# Attenuation.net
KiCad netlist of a schematic drawn in EAGLE
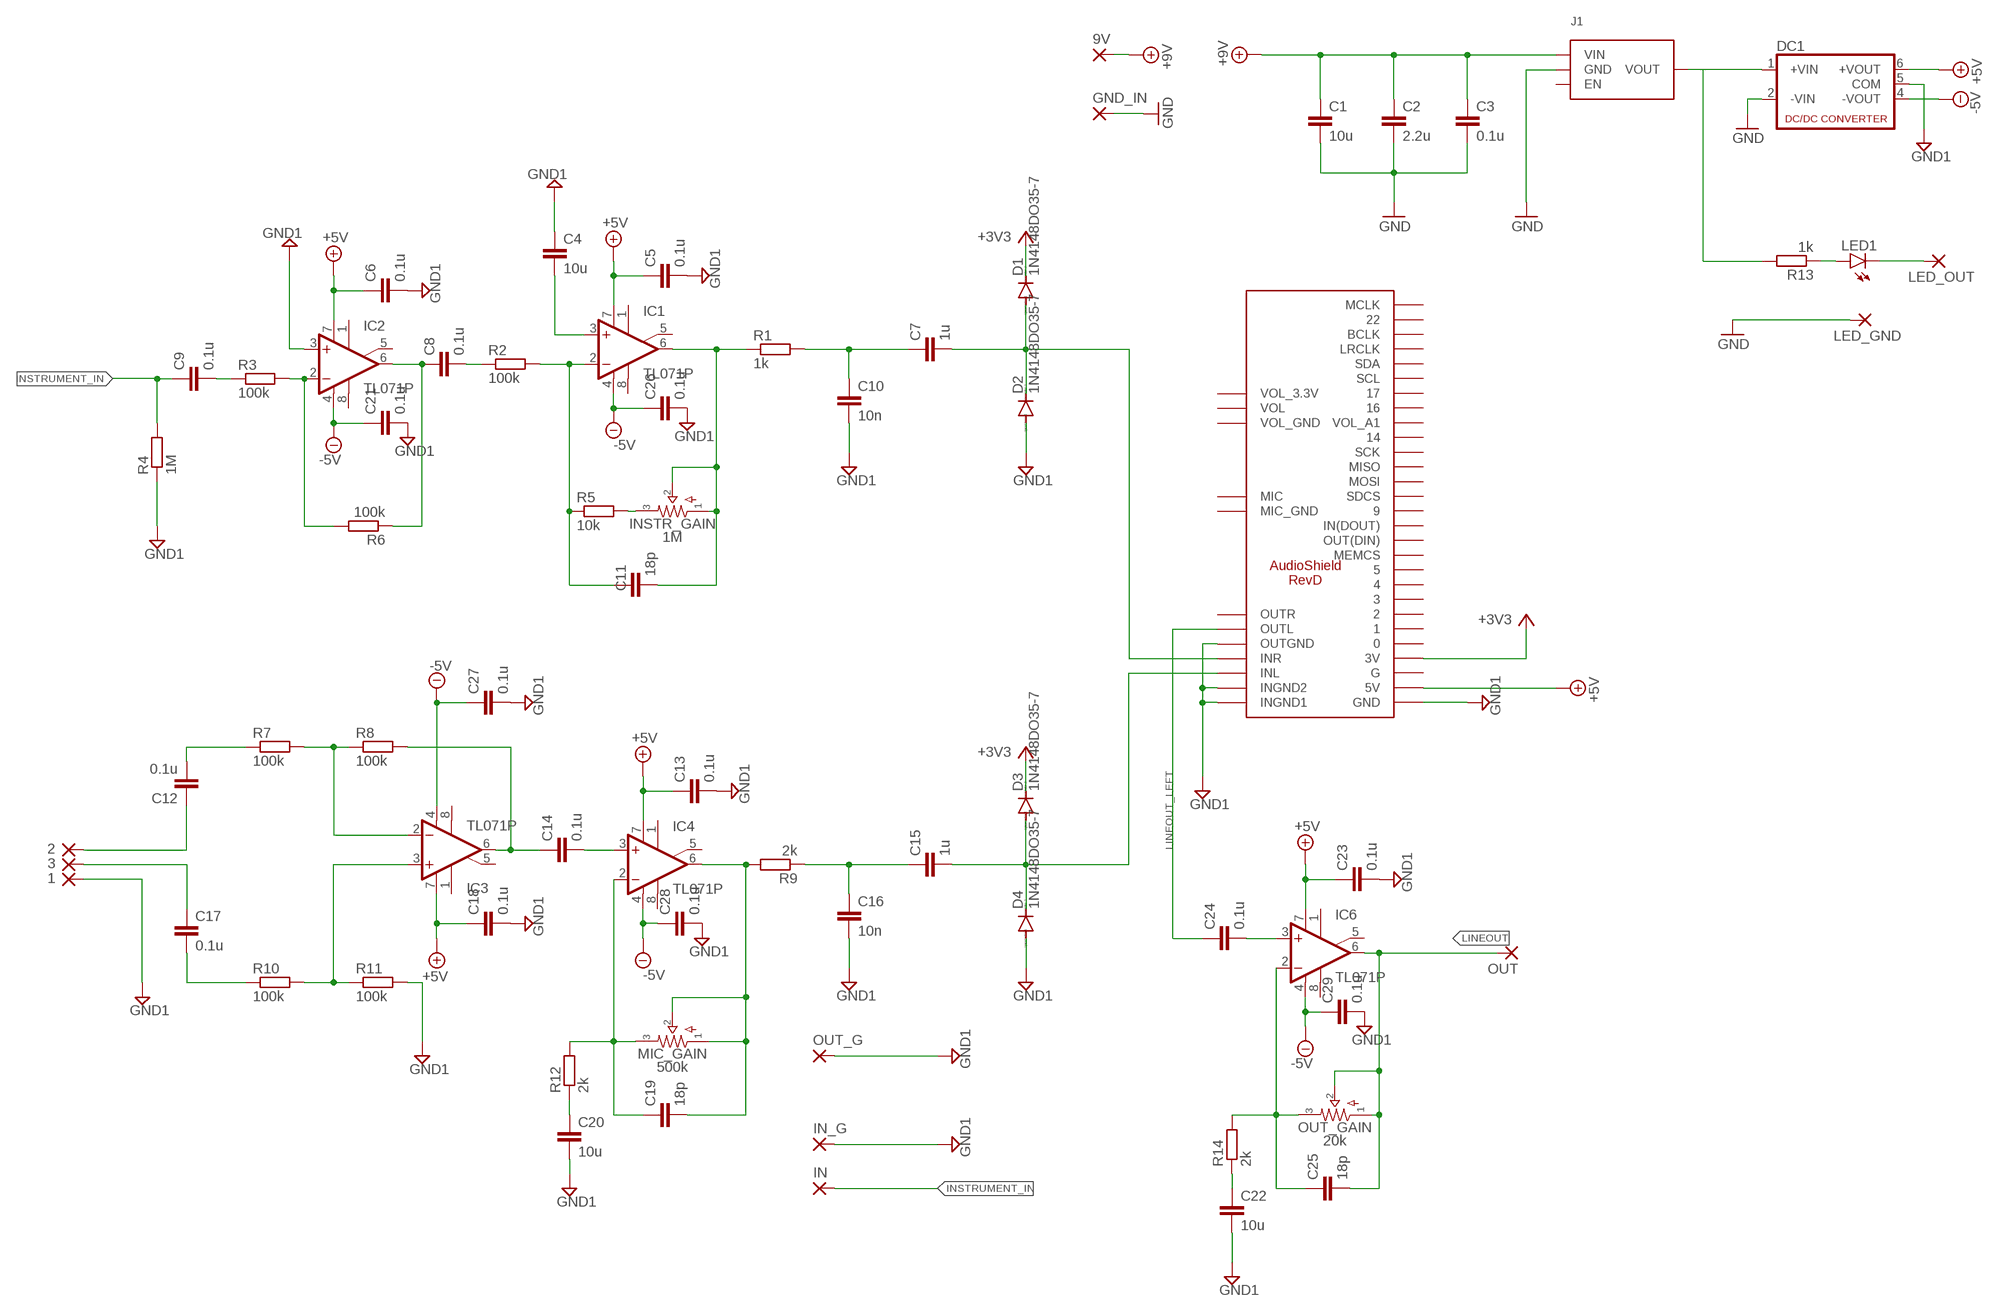
[diagram p0: schematic, sheet 1]

(export (version "E")
  (design (tool "Eeschema 10.0.6"))
  (components
    (comp (ref "1")
      (value "1,6/0,8")
      (footprint "eagle-import:1,6_0,8")
      (libsource (lib "eagle-import") (part "1,6/0,8"))
    )
    (comp (ref "2")
      (value "1,6/0,8")
      (footprint "eagle-import:1,6_0,8")
      (libsource (lib "eagle-import") (part "1,6/0,8"))
    )
    (comp (ref "3")
      (value "1,6/0,8")
      (footprint "eagle-import:1,6_0,8")
      (libsource (lib "eagle-import") (part "1,6/0,8"))
    )
    (comp (ref "9V")
      (value "1,6/0,8")
      (footprint "eagle-import:1,6_0,8")
      (libsource (lib "eagle-import") (part "1,6/0,8"))
    )
    (comp (ref "C1")
      (value "10u")
      (footprint "eagle-import:C5B2.5")
      (libsource (lib "eagle-import") (part "C5/2.5"))
    )
    (comp (ref "C2")
      (value "2.2u")
      (footprint "eagle-import:C5B2.5")
      (libsource (lib "eagle-import") (part "C5/2.5"))
    )
    (comp (ref "C3")
      (value "0.1u")
      (footprint "eagle-import:C0805")
      (libsource (lib "eagle-import") (part "C-EUC0805"))
    )
    (comp (ref "C4")
      (value "10u")
      (footprint "eagle-import:C5B2.5")
      (libsource (lib "eagle-import") (part "C5/2.5"))
    )
    (comp (ref "C5")
      (value "0.1u")
      (footprint "eagle-import:C0805")
      (libsource (lib "eagle-import") (part "C-EUC0805"))
    )
    (comp (ref "C6")
      (value "0.1u")
      (footprint "eagle-import:C0805")
      (libsource (lib "eagle-import") (part "C-EUC0805"))
    )
    (comp (ref "C7")
      (value "1u")
      (footprint "eagle-import:C0805")
      (libsource (lib "eagle-import") (part "C-EUC0805"))
    )
    (comp (ref "C8")
      (value "0.1u")
      (footprint "eagle-import:C0805")
      (libsource (lib "eagle-import") (part "C-EUC0805"))
    )
    (comp (ref "C9")
      (value "0.1u")
      (footprint "eagle-import:C0805")
      (libsource (lib "eagle-import") (part "C-EUC0805"))
    )
    (comp (ref "C10")
      (value "10n")
      (footprint "eagle-import:C0805")
      (libsource (lib "eagle-import") (part "C-EUC0805"))
    )
    (comp (ref "C11")
      (value "18p")
      (footprint "eagle-import:C0805")
      (libsource (lib "eagle-import") (part "C-EUC0805"))
    )
    (comp (ref "C12")
      (value "0.1u")
      (footprint "eagle-import:C0805")
      (libsource (lib "eagle-import") (part "C-EUC0805"))
    )
    (comp (ref "C13")
      (value "0.1u")
      (footprint "eagle-import:C0805")
      (libsource (lib "eagle-import") (part "C-EUC0805"))
    )
    (comp (ref "C14")
      (value "0.1u")
      (footprint "eagle-import:C0805")
      (libsource (lib "eagle-import") (part "C-EUC0805"))
    )
    (comp (ref "C15")
      (value "1u")
      (footprint "eagle-import:C0805")
      (libsource (lib "eagle-import") (part "C-EUC0805"))
    )
    (comp (ref "C16")
      (value "10n")
      (footprint "eagle-import:C0805")
      (libsource (lib "eagle-import") (part "C-EUC0805"))
    )
    (comp (ref "C17")
      (value "0.1u")
      (footprint "eagle-import:C0805")
      (libsource (lib "eagle-import") (part "C-EUC0805"))
    )
    (comp (ref "C18")
      (value "0.1u")
      (footprint "eagle-import:C0805")
      (libsource (lib "eagle-import") (part "C-EUC0805"))
    )
    (comp (ref "C19")
      (value "18p")
      (footprint "eagle-import:C0805")
      (libsource (lib "eagle-import") (part "C-EUC0805"))
    )
    (comp (ref "C20")
      (value "10u")
      (footprint "eagle-import:C5B2.5")
      (libsource (lib "eagle-import") (part "C5/2.5"))
    )
    (comp (ref "C21")
      (value "0.1u")
      (footprint "eagle-import:C0805")
      (libsource (lib "eagle-import") (part "C-EUC0805"))
    )
    (comp (ref "C22")
      (value "10u")
      (footprint "eagle-import:C5B2.5")
      (libsource (lib "eagle-import") (part "C5/2.5"))
    )
    (comp (ref "C23")
      (value "0.1u")
      (footprint "eagle-import:C0805")
      (libsource (lib "eagle-import") (part "C-EUC0805"))
    )
    (comp (ref "C24")
      (value "0.1u")
      (footprint "eagle-import:C0805")
      (libsource (lib "eagle-import") (part "C-EUC0805"))
    )
    (comp (ref "C25")
      (value "18p")
      (footprint "eagle-import:C0805")
      (libsource (lib "eagle-import") (part "C-EUC0805"))
    )
    (comp (ref "C26")
      (value "0.1u")
      (footprint "eagle-import:C0805")
      (libsource (lib "eagle-import") (part "C-EUC0805"))
    )
    (comp (ref "C27")
      (value "0.1u")
      (footprint "eagle-import:C0805")
      (libsource (lib "eagle-import") (part "C-EUC0805"))
    )
    (comp (ref "C28")
      (value "0.1u")
      (footprint "eagle-import:C0805")
      (libsource (lib "eagle-import") (part "C-EUC0805"))
    )
    (comp (ref "C29")
      (value "0.1u")
      (footprint "eagle-import:C0805")
      (libsource (lib "eagle-import") (part "C-EUC0805"))
    )
    (comp (ref "D1")
      (value "1N4148DO35-7")
      (footprint "eagle-import:DO35-7")
      (libsource (lib "eagle-import") (part "1N4148DO35-7"))
    )
    (comp (ref "D2")
      (value "1N4148DO35-7")
      (footprint "eagle-import:DO35-7")
      (libsource (lib "eagle-import") (part "1N4148DO35-7"))
    )
    (comp (ref "D3")
      (value "1N4148DO35-7")
      (footprint "eagle-import:DO35-7")
      (libsource (lib "eagle-import") (part "1N4148DO35-7"))
    )
    (comp (ref "D4")
      (value "1N4148DO35-7")
      (footprint "eagle-import:DO35-7")
      (libsource (lib "eagle-import") (part "1N4148DO35-7"))
    )
    (comp (ref "DC1")
      (value "NMA")
      (footprint "eagle-import:NMA")
      (fields (field (name "MF") "C & D TECHNOLOGIES, INC") (field (name "MPN") "NMA0515SC"))
      (libsource (lib "eagle-import") (part "NMA"))
    )
    (comp (ref "GND_IN")
      (value "1,6/0,8")
      (footprint "eagle-import:1,6_0,8")
      (libsource (lib "eagle-import") (part "1,6/0,8"))
    )
    (comp (ref "IC1")
      (value "TL071P")
      (footprint "eagle-import:DIL08")
      (libsource (lib "eagle-import") (part "TL071P"))
    )
    (comp (ref "IC2")
      (value "TL071P")
      (footprint "eagle-import:DIL08")
      (libsource (lib "eagle-import") (part "TL071P"))
    )
    (comp (ref "IC3")
      (value "TL071P")
      (footprint "eagle-import:DIL08")
      (libsource (lib "eagle-import") (part "TL071P"))
    )
    (comp (ref "IC4")
      (value "TL071P")
      (footprint "eagle-import:DIL08")
      (libsource (lib "eagle-import") (part "TL071P"))
    )
    (comp (ref "IC6")
      (value "TL071P")
      (footprint "eagle-import:DIL08")
      (libsource (lib "eagle-import") (part "TL071P"))
    )
    (comp (ref "IN")
      (value "1,6/0,8")
      (footprint "eagle-import:1,6_0,8")
      (libsource (lib "eagle-import") (part "1,6/0,8"))
    )
    (comp (ref "INSTR_GAIN")
      (value "1M")
      (footprint "eagle-import:16MM_PADS.1")
      (libsource (lib "eagle-import") (part "16MM.4"))
    )
    (comp (ref "IN_G")
      (value "1,6/0,8")
      (footprint "eagle-import:1,6_0,8")
      (libsource (lib "eagle-import") (part "1,6/0,8"))
    )
    (comp (ref "J1")
      (value "DCDC_MINI_CONVERTER")
      (footprint "eagle-import:DCDC_MINI_CONVERTER")
      (libsource (lib "eagle-import") (part "DCDC_MINI_CONVERTER"))
    )
    (comp (ref "LED1")
      (value "LED5MM")
      (footprint "eagle-import:LED5MM")
      (libsource (lib "eagle-import") (part "LED5MM"))
    )
    (comp (ref "LED_GND")
      (value "1,6/0,8")
      (footprint "eagle-import:1,6_0,8")
      (libsource (lib "eagle-import") (part "1,6/0,8"))
    )
    (comp (ref "LED_OUT")
      (value "1,6/0,8")
      (footprint "eagle-import:1,6_0,8")
      (libsource (lib "eagle-import") (part "1,6/0,8"))
    )
    (comp (ref "MIC_GAIN")
      (value "500k")
      (footprint "eagle-import:16MM_PADS.1")
      (libsource (lib "eagle-import") (part "16MM.4"))
    )
    (comp (ref "MOD1")
      (value "AUDIOSHIELD-REVD")
      (footprint "eagle-import:AUDIOSHIELD-REVD")
      (libsource (lib "eagle-import") (part "AUDIOSHIELD-REVD"))
    )
    (comp (ref "OUT")
      (value "1,6/0,8")
      (footprint "eagle-import:1,6_0,8")
      (libsource (lib "eagle-import") (part "1,6/0,8"))
    )
    (comp (ref "OUT_G")
      (value "1,6/0,8")
      (footprint "eagle-import:1,6_0,8")
      (libsource (lib "eagle-import") (part "1,6/0,8"))
    )
    (comp (ref "OUT_GAIN")
      (value "20k")
      (footprint "eagle-import:16MM_PADS.1")
      (libsource (lib "eagle-import") (part "16MM.4"))
    )
    (comp (ref "R1")
      (value "1k")
      (footprint "eagle-import:R0805")
      (libsource (lib "eagle-import") (part "R-EU_R0805"))
    )
    (comp (ref "R2")
      (value "100k")
      (footprint "eagle-import:R0805")
      (libsource (lib "eagle-import") (part "R-EU_R0805"))
    )
    (comp (ref "R3")
      (value "100k")
      (footprint "eagle-import:R0805")
      (libsource (lib "eagle-import") (part "R-EU_R0805"))
    )
    (comp (ref "R4")
      (value "1M")
      (footprint "eagle-import:R0805")
      (libsource (lib "eagle-import") (part "R-EU_R0805"))
    )
    (comp (ref "R5")
      (value "10k")
      (footprint "eagle-import:R0805")
      (libsource (lib "eagle-import") (part "R-EU_R0805"))
    )
    (comp (ref "R6")
      (value "100k")
      (footprint "eagle-import:R0805")
      (libsource (lib "eagle-import") (part "R-EU_R0805"))
    )
    (comp (ref "R7")
      (value "100k")
      (footprint "eagle-import:R0805")
      (libsource (lib "eagle-import") (part "R-EU_R0805"))
    )
    (comp (ref "R8")
      (value "100k")
      (footprint "eagle-import:R0805")
      (libsource (lib "eagle-import") (part "R-EU_R0805"))
    )
    (comp (ref "R9")
      (value "2k")
      (footprint "eagle-import:R0805")
      (libsource (lib "eagle-import") (part "R-EU_R0805"))
    )
    (comp (ref "R10")
      (value "100k")
      (footprint "eagle-import:R0805")
      (libsource (lib "eagle-import") (part "R-EU_R0805"))
    )
    (comp (ref "R11")
      (value "100k")
      (footprint "eagle-import:R0805")
      (libsource (lib "eagle-import") (part "R-EU_R0805"))
    )
    (comp (ref "R12")
      (value "2k")
      (footprint "eagle-import:R0805")
      (libsource (lib "eagle-import") (part "R-EU_R0805"))
    )
    (comp (ref "R13")
      (value "1k")
      (footprint "eagle-import:R0805")
      (libsource (lib "eagle-import") (part "R-EU_R0805"))
    )
    (comp (ref "R14")
      (value "2k")
      (footprint "eagle-import:R0805")
      (libsource (lib "eagle-import") (part "R-EU_R0805"))
    )
  )
  (nets
    (net (code "1") (name "+3V3") (class "Default")
      (node (ref "D1") (pin "C") (pinfunction "C_C") (pintype "passive"))
      (node (ref "D3") (pin "C") (pinfunction "C_C") (pintype "passive"))
      (node (ref "MOD1") (pin "3V") (pinfunction "3V_3V") (pintype "bidirectional"))
    )
    (net (code "2") (name "+5V") (class "Default")
      (node (ref "C13") (pin "1") (pinfunction "1_1") (pintype "passive"))
      (node (ref "C18") (pin "1") (pinfunction "1_1") (pintype "passive"))
      (node (ref "C23") (pin "1") (pinfunction "1_1") (pintype "passive"))
      (node (ref "C5") (pin "1") (pinfunction "1_1") (pintype "passive"))
      (node (ref "C6") (pin "1") (pinfunction "1_1") (pintype "passive"))
      (node (ref "DC1") (pin "6") (pinfunction "+VOUT_6") (pintype "passive"))
      (node (ref "IC1") (pin "7") (pinfunction "V+_7") (pintype "power_in"))
      (node (ref "IC2") (pin "7") (pinfunction "V+_7") (pintype "power_in"))
      (node (ref "IC3") (pin "7") (pinfunction "V+_7") (pintype "power_in"))
      (node (ref "IC4") (pin "7") (pinfunction "V+_7") (pintype "power_in"))
      (node (ref "IC6") (pin "7") (pinfunction "V+_7") (pintype "power_in"))
      (node (ref "MOD1") (pin "5V") (pinfunction "5V_5V") (pintype "bidirectional"))
    )
    (net (code "3") (name "+9V") (class "Default")
      (node (ref "9V") (pin "1") (pinfunction "P_1") (pintype "passive"))
      (node (ref "C1") (pin "1") (pinfunction "1_1") (pintype "passive"))
      (node (ref "C2") (pin "1") (pinfunction "1_1") (pintype "passive"))
      (node (ref "C3") (pin "1") (pinfunction "1_1") (pintype "passive"))
      (node (ref "J1") (pin "VIN") (pinfunction "VIN_VIN") (pintype "bidirectional"))
    )
    (net (code "4") (name "-5V") (class "Default")
      (node (ref "C21") (pin "1") (pinfunction "1_1") (pintype "passive"))
      (node (ref "C26") (pin "1") (pinfunction "1_1") (pintype "passive"))
      (node (ref "C27") (pin "1") (pinfunction "1_1") (pintype "passive"))
      (node (ref "C28") (pin "1") (pinfunction "1_1") (pintype "passive"))
      (node (ref "C29") (pin "1") (pinfunction "1_1") (pintype "passive"))
      (node (ref "DC1") (pin "4") (pinfunction "-VOUT_4") (pintype "passive"))
      (node (ref "IC1") (pin "4") (pinfunction "V-_4") (pintype "power_in"))
      (node (ref "IC2") (pin "4") (pinfunction "V-_4") (pintype "power_in"))
      (node (ref "IC3") (pin "4") (pinfunction "V-_4") (pintype "power_in"))
      (node (ref "IC4") (pin "4") (pinfunction "V-_4") (pintype "power_in"))
      (node (ref "IC6") (pin "4") (pinfunction "V-_4") (pintype "power_in"))
    )
    (net (code "5") (name "/LINEOUT_LEFT") (class "Default")
      (node (ref "C24") (pin "1") (pinfunction "1_1") (pintype "passive"))
      (node (ref "MOD1") (pin "OUTL") (pinfunction "OUTL_OUTL") (pintype "output"))
    )
    (net (code "6") (name "GND") (class "Default")
      (node (ref "C1") (pin "2") (pinfunction "2_2") (pintype "passive"))
      (node (ref "C2") (pin "2") (pinfunction "2_2") (pintype "passive"))
      (node (ref "C3") (pin "2") (pinfunction "2_2") (pintype "passive"))
      (node (ref "DC1") (pin "2") (pinfunction "-VIN_2") (pintype "passive"))
      (node (ref "GND_IN") (pin "1") (pinfunction "P_1") (pintype "passive"))
      (node (ref "J1") (pin "GND") (pinfunction "GND_GND") (pintype "bidirectional"))
      (node (ref "LED_GND") (pin "1") (pinfunction "P_1") (pintype "passive"))
    )
    (net (code "7") (name "GND1") (class "Default")
      (node (ref "1") (pin "1") (pinfunction "P_1") (pintype "passive"))
      (node (ref "C10") (pin "2") (pinfunction "2_2") (pintype "passive"))
      (node (ref "C13") (pin "2") (pinfunction "2_2") (pintype "passive"))
      (node (ref "C16") (pin "2") (pinfunction "2_2") (pintype "passive"))
      (node (ref "C18") (pin "2") (pinfunction "2_2") (pintype "passive"))
      (node (ref "C20") (pin "2") (pinfunction "2_2") (pintype "passive"))
      (node (ref "C21") (pin "2") (pinfunction "2_2") (pintype "passive"))
      (node (ref "C22") (pin "2") (pinfunction "2_2") (pintype "passive"))
      (node (ref "C23") (pin "2") (pinfunction "2_2") (pintype "passive"))
      (node (ref "C26") (pin "2") (pinfunction "2_2") (pintype "passive"))
      (node (ref "C27") (pin "2") (pinfunction "2_2") (pintype "passive"))
      (node (ref "C28") (pin "2") (pinfunction "2_2") (pintype "passive"))
      (node (ref "C29") (pin "2") (pinfunction "2_2") (pintype "passive"))
      (node (ref "C4") (pin "1") (pinfunction "1_1") (pintype "passive"))
      (node (ref "C5") (pin "2") (pinfunction "2_2") (pintype "passive"))
      (node (ref "C6") (pin "2") (pinfunction "2_2") (pintype "passive"))
      (node (ref "D2") (pin "A") (pinfunction "A_A") (pintype "passive"))
      (node (ref "D4") (pin "A") (pinfunction "A_A") (pintype "passive"))
      (node (ref "DC1") (pin "5") (pinfunction "COM_5") (pintype "passive"))
      (node (ref "IC2") (pin "3") (pinfunction "+IN_3") (pintype "input"))
      (node (ref "IN_G") (pin "1") (pinfunction "P_1") (pintype "passive"))
      (node (ref "MOD1") (pin "GND") (pinfunction "GND_GND") (pintype "bidirectional"))
      (node (ref "MOD1") (pin "INGND1") (pinfunction "INGND1_INGND1") (pintype "bidirectional"))
      (node (ref "MOD1") (pin "INGND2") (pinfunction "INGND2_INGND2") (pintype "bidirectional"))
      (node (ref "MOD1") (pin "OUTGND") (pinfunction "OUTGND_OUTGND") (pintype "bidirectional"))
      (node (ref "OUT_G") (pin "1") (pinfunction "P_1") (pintype "passive"))
      (node (ref "R11") (pin "2") (pinfunction "2_2") (pintype "passive"))
      (node (ref "R4") (pin "1") (pinfunction "1_1") (pintype "passive"))
    )
    (net (code "8") (name "INSTRUMENT_IN") (class "Default")
      (node (ref "C9") (pin "1") (pinfunction "1_1") (pintype "passive"))
      (node (ref "IN") (pin "1") (pinfunction "P_1") (pintype "passive"))
      (node (ref "R4") (pin "2") (pinfunction "2_2") (pintype "passive"))
    )
    (net (code "9") (name "LINEOUT") (class "Default")
      (node (ref "C25") (pin "2") (pinfunction "2_2") (pintype "passive"))
      (node (ref "IC6") (pin "6") (pinfunction "OUT_6") (pintype "output"))
      (node (ref "OUT") (pin "1") (pinfunction "P_1") (pintype "passive"))
      (node (ref "OUT_GAIN") (pin "1") (pinfunction "1_1") (pintype "passive"))
      (node (ref "OUT_GAIN") (pin "2") (pinfunction "2_2") (pintype "passive"))
    )
    (net (code "10") (name "Net-(2-P)") (class "Default")
      (node (ref "2") (pin "1") (pinfunction "P_1") (pintype "passive"))
      (node (ref "C12") (pin "1") (pinfunction "1_1") (pintype "passive"))
    )
    (net (code "11") (name "Net-(3-P)") (class "Default")
      (node (ref "3") (pin "1") (pinfunction "P_1") (pintype "passive"))
      (node (ref "C17") (pin "1") (pinfunction "1_1") (pintype "passive"))
    )
    (net (code "12") (name "Net-(C7-Pad2)") (class "Default")
      (node (ref "C7") (pin "2") (pinfunction "2_2") (pintype "passive"))
      (node (ref "D1") (pin "A") (pinfunction "A_A") (pintype "passive"))
      (node (ref "D2") (pin "C") (pinfunction "C_C") (pintype "passive"))
      (node (ref "MOD1") (pin "INR") (pinfunction "INR_INR") (pintype "input"))
    )
    (net (code "13") (name "Net-(C8-Pad2)") (class "Default")
      (node (ref "C8") (pin "2") (pinfunction "2_2") (pintype "passive"))
      (node (ref "R2") (pin "1") (pinfunction "1_1") (pintype "passive"))
    )
    (net (code "14") (name "Net-(C9-Pad2)") (class "Default")
      (node (ref "C9") (pin "2") (pinfunction "2_2") (pintype "passive"))
      (node (ref "R3") (pin "1") (pinfunction "1_1") (pintype "passive"))
    )
    (net (code "15") (name "Net-(C10-Pad1)") (class "Default")
      (node (ref "C10") (pin "1") (pinfunction "1_1") (pintype "passive"))
      (node (ref "C7") (pin "1") (pinfunction "1_1") (pintype "passive"))
      (node (ref "R1") (pin "2") (pinfunction "2_2") (pintype "passive"))
    )
    (net (code "16") (name "Net-(C12-Pad2)") (class "Default")
      (node (ref "C12") (pin "2") (pinfunction "2_2") (pintype "passive"))
      (node (ref "R7") (pin "1") (pinfunction "1_1") (pintype "passive"))
    )
    (net (code "17") (name "Net-(C15-Pad1)") (class "Default")
      (node (ref "C15") (pin "1") (pinfunction "1_1") (pintype "passive"))
      (node (ref "C16") (pin "1") (pinfunction "1_1") (pintype "passive"))
      (node (ref "R9") (pin "1") (pinfunction "1_1") (pintype "passive"))
    )
    (net (code "18") (name "Net-(C15-Pad2)") (class "Default")
      (node (ref "C15") (pin "2") (pinfunction "2_2") (pintype "passive"))
      (node (ref "D3") (pin "A") (pinfunction "A_A") (pintype "passive"))
      (node (ref "D4") (pin "C") (pinfunction "C_C") (pintype "passive"))
      (node (ref "MOD1") (pin "INL") (pinfunction "INL_INL") (pintype "input"))
    )
    (net (code "19") (name "Net-(C17-Pad2)") (class "Default")
      (node (ref "C17") (pin "2") (pinfunction "2_2") (pintype "passive"))
      (node (ref "R10") (pin "1") (pinfunction "1_1") (pintype "passive"))
    )
    (net (code "20") (name "Net-(C20-Pad1)") (class "Default")
      (node (ref "C20") (pin "1") (pinfunction "1_1") (pintype "passive"))
      (node (ref "R12") (pin "1") (pinfunction "1_1") (pintype "passive"))
    )
    (net (code "21") (name "Net-(C22-Pad1)") (class "Default")
      (node (ref "C22") (pin "1") (pinfunction "1_1") (pintype "passive"))
      (node (ref "R14") (pin "1") (pinfunction "1_1") (pintype "passive"))
    )
    (net (code "22") (name "Net-(DC1-+VIN)") (class "Default")
      (node (ref "DC1") (pin "1") (pinfunction "+VIN_1") (pintype "passive"))
      (node (ref "J1") (pin "VOUT") (pinfunction "VOUT_VOUT") (pintype "bidirectional"))
      (node (ref "R13") (pin "2") (pinfunction "2_2") (pintype "passive"))
    )
    (net (code "23") (name "Net-(IC1-+IN)") (class "Default")
      (node (ref "C4") (pin "2") (pinfunction "2_2") (pintype "passive"))
      (node (ref "IC1") (pin "3") (pinfunction "+IN_3") (pintype "input"))
    )
    (net (code "24") (name "Net-(IC1--IN)") (class "Default")
      (node (ref "C11") (pin "1") (pinfunction "1_1") (pintype "passive"))
      (node (ref "IC1") (pin "2") (pinfunction "-IN_2") (pintype "input"))
      (node (ref "R2") (pin "2") (pinfunction "2_2") (pintype "passive"))
      (node (ref "R5") (pin "1") (pinfunction "1_1") (pintype "passive"))
    )
    (net (code "25") (name "Net-(IC1-OUT)") (class "Default")
      (node (ref "C11") (pin "2") (pinfunction "2_2") (pintype "passive"))
      (node (ref "IC1") (pin "6") (pinfunction "OUT_6") (pintype "output"))
      (node (ref "INSTR_GAIN") (pin "1") (pinfunction "1_1") (pintype "passive"))
      (node (ref "INSTR_GAIN") (pin "2") (pinfunction "2_2") (pintype "passive"))
      (node (ref "R1") (pin "1") (pinfunction "1_1") (pintype "passive"))
    )
    (net (code "26") (name "Net-(IC2--IN)") (class "Default")
      (node (ref "IC2") (pin "2") (pinfunction "-IN_2") (pintype "input"))
      (node (ref "R3") (pin "2") (pinfunction "2_2") (pintype "passive"))
      (node (ref "R6") (pin "2") (pinfunction "2_2") (pintype "passive"))
    )
    (net (code "27") (name "Net-(IC2-OUT)") (class "Default")
      (node (ref "C8") (pin "1") (pinfunction "1_1") (pintype "passive"))
      (node (ref "IC2") (pin "6") (pinfunction "OUT_6") (pintype "output"))
      (node (ref "R6") (pin "1") (pinfunction "1_1") (pintype "passive"))
    )
    (net (code "28") (name "Net-(IC3-+IN)") (class "Default")
      (node (ref "IC3") (pin "3") (pinfunction "+IN_3") (pintype "input"))
      (node (ref "R10") (pin "2") (pinfunction "2_2") (pintype "passive"))
      (node (ref "R11") (pin "1") (pinfunction "1_1") (pintype "passive"))
    )
    (net (code "29") (name "Net-(IC3--IN)") (class "Default")
      (node (ref "IC3") (pin "2") (pinfunction "-IN_2") (pintype "input"))
      (node (ref "R7") (pin "2") (pinfunction "2_2") (pintype "passive"))
      (node (ref "R8") (pin "1") (pinfunction "1_1") (pintype "passive"))
    )
    (net (code "30") (name "Net-(IC3-OUT)") (class "Default")
      (node (ref "C14") (pin "1") (pinfunction "1_1") (pintype "passive"))
      (node (ref "IC3") (pin "6") (pinfunction "OUT_6") (pintype "output"))
      (node (ref "R8") (pin "2") (pinfunction "2_2") (pintype "passive"))
    )
    (net (code "31") (name "Net-(IC4-+IN)") (class "Default")
      (node (ref "C14") (pin "2") (pinfunction "2_2") (pintype "passive"))
      (node (ref "IC4") (pin "3") (pinfunction "+IN_3") (pintype "input"))
    )
    (net (code "32") (name "Net-(IC4--IN)") (class "Default")
      (node (ref "C19") (pin "1") (pinfunction "1_1") (pintype "passive"))
      (node (ref "IC4") (pin "2") (pinfunction "-IN_2") (pintype "input"))
      (node (ref "MIC_GAIN") (pin "3") (pinfunction "3_3") (pintype "passive"))
      (node (ref "R12") (pin "2") (pinfunction "2_2") (pintype "passive"))
    )
    (net (code "33") (name "Net-(IC4-OUT)") (class "Default")
      (node (ref "C19") (pin "2") (pinfunction "2_2") (pintype "passive"))
      (node (ref "IC4") (pin "6") (pinfunction "OUT_6") (pintype "output"))
      (node (ref "MIC_GAIN") (pin "1") (pinfunction "1_1") (pintype "passive"))
      (node (ref "MIC_GAIN") (pin "2") (pinfunction "2_2") (pintype "passive"))
      (node (ref "R9") (pin "2") (pinfunction "2_2") (pintype "passive"))
    )
    (net (code "34") (name "Net-(IC6-+IN)") (class "Default")
      (node (ref "C24") (pin "2") (pinfunction "2_2") (pintype "passive"))
      (node (ref "IC6") (pin "3") (pinfunction "+IN_3") (pintype "input"))
    )
    (net (code "35") (name "Net-(IC6--IN)") (class "Default")
      (node (ref "C25") (pin "1") (pinfunction "1_1") (pintype "passive"))
      (node (ref "IC6") (pin "2") (pinfunction "-IN_2") (pintype "input"))
      (node (ref "OUT_GAIN") (pin "3") (pinfunction "3_3") (pintype "passive"))
      (node (ref "R14") (pin "2") (pinfunction "2_2") (pintype "passive"))
    )
    (net (code "36") (name "Net-(INSTR_GAIN-Pad3)") (class "Default")
      (node (ref "INSTR_GAIN") (pin "3") (pinfunction "3_3") (pintype "passive"))
      (node (ref "R5") (pin "2") (pinfunction "2_2") (pintype "passive"))
    )
    (net (code "37") (name "Net-(LED1-C)") (class "Default")
      (node (ref "LED1") (pin "K") (pinfunction "C_K") (pintype "passive"))
      (node (ref "LED_OUT") (pin "1") (pinfunction "P_1") (pintype "passive"))
    )
    (net (code "38") (name "Net-(LED1-PadA)") (class "Default")
      (node (ref "LED1") (pin "A") (pinfunction "A_A") (pintype "passive"))
      (node (ref "R13") (pin "1") (pinfunction "1_1") (pintype "passive"))
    )
    (net (code "39") (name "unconnected-(IC1-ON1-Pad1)") (class "Default")
      (node (ref "IC1") (pin "1") (pinfunction "ON1_1") (pintype "passive"))
    )
    (net (code "40") (name "unconnected-(IC1-ON2-Pad5)") (class "Default")
      (node (ref "IC1") (pin "5") (pinfunction "ON2_5") (pintype "passive"))
    )
    (net (code "41") (name "unconnected-(IC1-OPT-Pad8)") (class "Default")
      (node (ref "IC1") (pin "8") (pinfunction "OPT_8") (pintype "passive"))
    )
    (net (code "42") (name "unconnected-(IC2-ON1-Pad1)") (class "Default")
      (node (ref "IC2") (pin "1") (pinfunction "ON1_1") (pintype "passive"))
    )
    (net (code "43") (name "unconnected-(IC2-ON2-Pad5)") (class "Default")
      (node (ref "IC2") (pin "5") (pinfunction "ON2_5") (pintype "passive"))
    )
    (net (code "44") (name "unconnected-(IC2-OPT-Pad8)") (class "Default")
      (node (ref "IC2") (pin "8") (pinfunction "OPT_8") (pintype "passive"))
    )
    (net (code "45") (name "unconnected-(IC3-ON1-Pad1)") (class "Default")
      (node (ref "IC3") (pin "1") (pinfunction "ON1_1") (pintype "passive"))
    )
    (net (code "46") (name "unconnected-(IC3-ON2-Pad5)") (class "Default")
      (node (ref "IC3") (pin "5") (pinfunction "ON2_5") (pintype "passive"))
    )
    (net (code "47") (name "unconnected-(IC3-OPT-Pad8)") (class "Default")
      (node (ref "IC3") (pin "8") (pinfunction "OPT_8") (pintype "passive"))
    )
    (net (code "48") (name "unconnected-(IC4-ON1-Pad1)") (class "Default")
      (node (ref "IC4") (pin "1") (pinfunction "ON1_1") (pintype "passive"))
    )
    (net (code "49") (name "unconnected-(IC4-ON2-Pad5)") (class "Default")
      (node (ref "IC4") (pin "5") (pinfunction "ON2_5") (pintype "passive"))
    )
    (net (code "50") (name "unconnected-(IC4-OPT-Pad8)") (class "Default")
      (node (ref "IC4") (pin "8") (pinfunction "OPT_8") (pintype "passive"))
    )
    (net (code "51") (name "unconnected-(IC6-ON1-Pad1)") (class "Default")
      (node (ref "IC6") (pin "1") (pinfunction "ON1_1") (pintype "passive"))
    )
    (net (code "52") (name "unconnected-(IC6-ON2-Pad5)") (class "Default")
      (node (ref "IC6") (pin "5") (pinfunction "ON2_5") (pintype "passive"))
    )
    (net (code "53") (name "unconnected-(IC6-OPT-Pad8)") (class "Default")
      (node (ref "IC6") (pin "8") (pinfunction "OPT_8") (pintype "passive"))
    )
    (net (code "54") (name "unconnected-(J1-PadEN)") (class "Default")
      (node (ref "J1") (pin "EN") (pinfunction "EN_EN") (pintype "bidirectional"))
    )
    (net (code "55") (name "unconnected-(MOD1-BCLK-Pad21)") (class "Default")
      (node (ref "MOD1") (pin "21") (pinfunction "BCLK_21") (pintype "bidirectional"))
    )
    (net (code "56") (name "unconnected-(MOD1-IN(DOUT)-Pad8)") (class "Default")
      (node (ref "MOD1") (pin "8") (pinfunction "IN(DOUT)_8") (pintype "bidirectional"))
    )
    (net (code "57") (name "unconnected-(MOD1-LRCLK-Pad20)") (class "Default")
      (node (ref "MOD1") (pin "20") (pinfunction "LRCLK_20") (pintype "bidirectional"))
    )
    (net (code "58") (name "unconnected-(MOD1-MCLK-Pad23)") (class "Default")
      (node (ref "MOD1") (pin "23") (pinfunction "MCLK_23") (pintype "bidirectional"))
    )
    (net (code "59") (name "unconnected-(MOD1-MEMCS-Pad6)") (class "Default")
      (node (ref "MOD1") (pin "6") (pinfunction "MEMCS_6") (pintype "bidirectional"))
    )
    (net (code "60") (name "unconnected-(MOD1-MIC_GND-PadGND_MIC)") (class "Default")
      (node (ref "MOD1") (pin "GND_MIC") (pinfunction "MIC_GND_GND_MIC") (pintype "bidirectional"))
    )
    (net (code "61") (name "unconnected-(MOD1-MISO-Pad12)") (class "Default")
      (node (ref "MOD1") (pin "12") (pinfunction "MISO_12") (pintype "bidirectional"))
    )
    (net (code "62") (name "unconnected-(MOD1-MOSI-Pad11)") (class "Default")
      (node (ref "MOD1") (pin "11") (pinfunction "MOSI_11") (pintype "bidirectional"))
    )
    (net (code "63") (name "unconnected-(MOD1-OUT(DIN)-Pad7)") (class "Default")
      (node (ref "MOD1") (pin "7") (pinfunction "OUT(DIN)_7") (pintype "bidirectional"))
    )
    (net (code "64") (name "unconnected-(MOD1-Pad0)") (class "Default")
      (node (ref "MOD1") (pin "0") (pinfunction "0_0") (pintype "bidirectional"))
    )
    (net (code "65") (name "unconnected-(MOD1-Pad1)") (class "Default")
      (node (ref "MOD1") (pin "1") (pinfunction "1_1") (pintype "bidirectional"))
    )
    (net (code "66") (name "unconnected-(MOD1-Pad2)") (class "Default")
      (node (ref "MOD1") (pin "2") (pinfunction "2_2") (pintype "bidirectional"))
    )
    (net (code "67") (name "unconnected-(MOD1-Pad3)") (class "Default")
      (node (ref "MOD1") (pin "3") (pinfunction "3_3") (pintype "bidirectional"))
    )
    (net (code "68") (name "unconnected-(MOD1-Pad4)") (class "Default")
      (node (ref "MOD1") (pin "4") (pinfunction "4_4") (pintype "bidirectional"))
    )
    (net (code "69") (name "unconnected-(MOD1-Pad5)") (class "Default")
      (node (ref "MOD1") (pin "5") (pinfunction "5_5") (pintype "bidirectional"))
    )
    (net (code "70") (name "unconnected-(MOD1-Pad9)") (class "Default")
      (node (ref "MOD1") (pin "9") (pinfunction "9_9") (pintype "bidirectional"))
    )
    (net (code "71") (name "unconnected-(MOD1-Pad14)") (class "Default")
      (node (ref "MOD1") (pin "14") (pinfunction "14_14") (pintype "bidirectional"))
    )
    (net (code "72") (name "unconnected-(MOD1-Pad16)") (class "Default")
      (node (ref "MOD1") (pin "16") (pinfunction "16_16") (pintype "bidirectional"))
    )
    (net (code "73") (name "unconnected-(MOD1-Pad17)") (class "Default")
      (node (ref "MOD1") (pin "17") (pinfunction "17_17") (pintype "bidirectional"))
    )
    (net (code "74") (name "unconnected-(MOD1-Pad22)") (class "Default")
      (node (ref "MOD1") (pin "22") (pinfunction "22_22") (pintype "bidirectional"))
    )
    (net (code "75") (name "unconnected-(MOD1-PadG)") (class "Default")
      (node (ref "MOD1") (pin "G") (pinfunction "G_G") (pintype "bidirectional"))
    )
    (net (code "76") (name "unconnected-(MOD1-PadMIC)") (class "Default")
      (node (ref "MOD1") (pin "MIC") (pinfunction "MIC_MIC") (pintype "input"))
    )
    (net (code "77") (name "unconnected-(MOD1-PadOUTR)") (class "Default")
      (node (ref "MOD1") (pin "OUTR") (pinfunction "OUTR_OUTR") (pintype "output"))
    )
    (net (code "78") (name "unconnected-(MOD1-PadVOL)") (class "Default")
      (node (ref "MOD1") (pin "VOL") (pinfunction "VOL_VOL") (pintype "input"))
    )
    (net (code "79") (name "unconnected-(MOD1-PadVOL_3.3V)") (class "Default")
      (node (ref "MOD1") (pin "VOL_3.3V") (pinfunction "VOL_3.3V_VOL_3.3V") (pintype "bidirectional"))
    )
    (net (code "80") (name "unconnected-(MOD1-PadVOL_GND)") (class "Default")
      (node (ref "MOD1") (pin "VOL_GND") (pinfunction "VOL_GND_VOL_GND") (pintype "bidirectional"))
    )
    (net (code "81") (name "unconnected-(MOD1-SCK-Pad13)") (class "Default")
      (node (ref "MOD1") (pin "13") (pinfunction "SCK_13") (pintype "bidirectional"))
    )
    (net (code "82") (name "unconnected-(MOD1-SCL-Pad19)") (class "Default")
      (node (ref "MOD1") (pin "19") (pinfunction "SCL_19") (pintype "bidirectional"))
    )
    (net (code "83") (name "unconnected-(MOD1-SDA-Pad18)") (class "Default")
      (node (ref "MOD1") (pin "18") (pinfunction "SDA_18") (pintype "bidirectional"))
    )
    (net (code "84") (name "unconnected-(MOD1-SDCS-Pad10)") (class "Default")
      (node (ref "MOD1") (pin "10") (pinfunction "SDCS_10") (pintype "bidirectional"))
    )
    (net (code "85") (name "unconnected-(MOD1-VOL_A1-Pad15)") (class "Default")
      (node (ref "MOD1") (pin "15") (pinfunction "VOL_A1_15") (pintype "bidirectional"))
    )
  )
)
